# 51control.net
KiCad netlist of a schematic drawn in Altium Designer
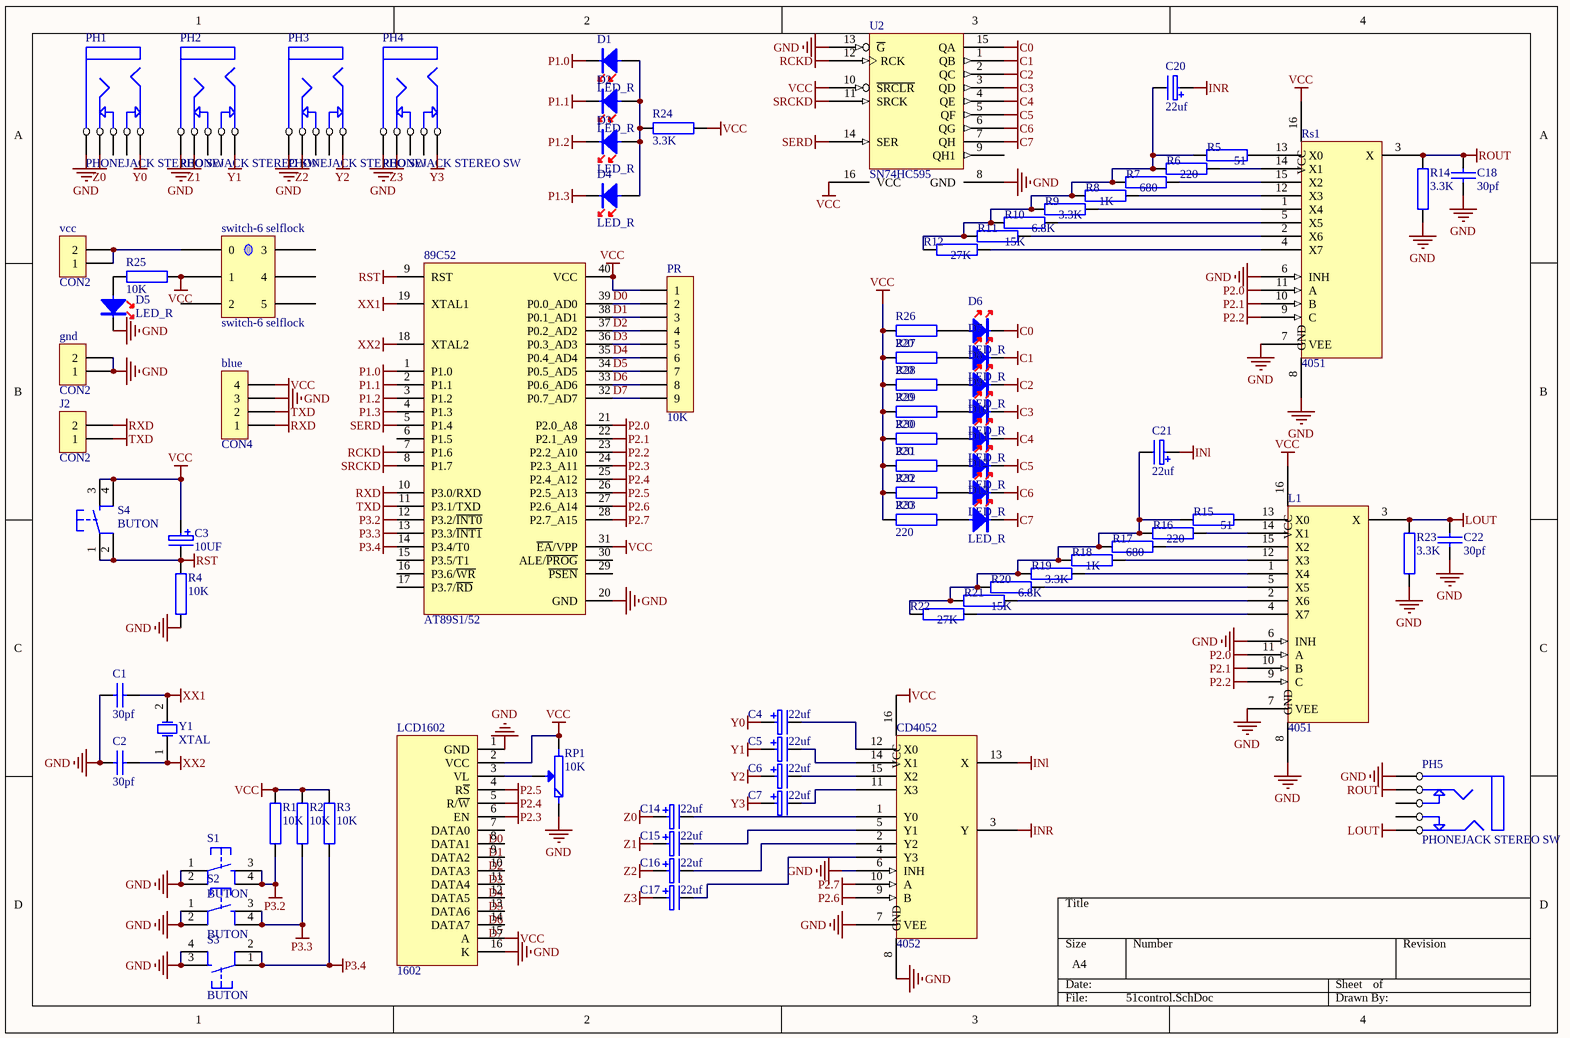
[diagram p0: 51control.SchDoc]

(export (version "E")
  (design (tool "Eeschema 10.0.6"))
  (components
    (comp (ref "89C52")
      (value "AT89S1/52")
      (footprint "DIP40")
      (description "8051/52单片机")
      (libsource (lib "常用元件集成库") (part "AT89S1/52"))
    )
    (comp (ref "blue")
      (value "CON4")
      (footprint "sip-4")
      (description "Connector")
      (libsource (lib "排针") (part "CON4"))
    )
    (comp (ref "C1") (value "30pf") (footprint "0603") (libsource (lib "电容") (part "CAP1")))
    (comp (ref "C2") (value "30pf") (footprint "0603") (libsource (lib "电容") (part "CAP1")))
    (comp (ref "C3") (value "10UF") (footprint "CAO2") (libsource (lib "电容") (part "CAP3")))
    (comp (ref "C4") (value "22uf") (footprint "CAO2") (libsource (lib "电容") (part "CAP3")))
    (comp (ref "C5") (value "22uf") (footprint "CAO2") (libsource (lib "电容") (part "CAP3")))
    (comp (ref "C6") (value "22uf") (footprint "CAO2") (libsource (lib "电容") (part "CAP3")))
    (comp (ref "C7") (value "22uf") (footprint "CAO2") (libsource (lib "电容") (part "CAP3")))
    (comp (ref "C14") (value "22uf") (footprint "CAO2") (libsource (lib "电容") (part "CAP3")))
    (comp (ref "C15") (value "22uf") (footprint "CAO2") (libsource (lib "电容") (part "CAP3")))
    (comp (ref "C16") (value "22uf") (footprint "CAO2") (libsource (lib "电容") (part "CAP3")))
    (comp (ref "C17") (value "22uf") (footprint "CAO2") (libsource (lib "电容") (part "CAP3")))
    (comp (ref "C18") (value "30pf") (footprint "0603") (libsource (lib "电容") (part "CAP1")))
    (comp (ref "C20") (value "22uf") (footprint "CAO2") (libsource (lib "电容") (part "CAP3")))
    (comp (ref "C21") (value "22uf") (footprint "CAO2") (libsource (lib "电容") (part "CAP3")))
    (comp (ref "C22") (value "30pf") (footprint "0603") (libsource (lib "电容") (part "CAP1")))
    (comp (ref "CD4052") (value "4052") (footprint "CD4052") (libsource (lib "常用元件原理图库") (part "4052")))
    (comp (ref "D1") (value "LED_R") (footprint "LED2_R") (libsource (lib "Diode二极管") (part "LED_R")))
    (comp (ref "D2") (value "LED_R") (footprint "LED2_R") (libsource (lib "Diode二极管") (part "LED_R")))
    (comp (ref "D3") (value "LED_R") (footprint "LED2_R") (libsource (lib "Diode二极管") (part "LED_R")))
    (comp (ref "D4") (value "LED_R") (footprint "LED2_R") (libsource (lib "Diode二极管") (part "LED_R")))
    (comp (ref "D5") (value "LED_R") (footprint "LED_0805") (libsource (lib "Diode二极管") (part "LED_R")))
    (comp (ref "D6") (value "LED_R") (footprint "LED_0805") (libsource (lib "Diode二极管") (part "LED_R")))
    (comp (ref "D7") (value "LED_R") (footprint "LED_0805") (libsource (lib "Diode二极管") (part "LED_R")))
    (comp (ref "D8") (value "LED_R") (footprint "LED_0805") (libsource (lib "Diode二极管") (part "LED_R")))
    (comp (ref "D9") (value "LED_R") (footprint "LED_0805") (libsource (lib "Diode二极管") (part "LED_R")))
    (comp (ref "D10") (value "LED_R") (footprint "LED_0805") (libsource (lib "Diode二极管") (part "LED_R")))
    (comp (ref "D11") (value "LED_R") (footprint "LED_0805") (libsource (lib "Diode二极管") (part "LED_R")))
    (comp (ref "D12") (value "LED_R") (footprint "LED_0805") (libsource (lib "Diode二极管") (part "LED_R")))
    (comp (ref "D13") (value "LED_R") (footprint "LED_0805") (libsource (lib "Diode二极管") (part "LED_R")))
    (comp (ref "gnd")
      (value "CON2")
      (footprint "2P-200")
      (description "Connector")
      (libsource (lib "排针") (part "CON2"))
    )
    (comp (ref "J2")
      (value "CON2")
      (footprint "sip-2")
      (description "Connector")
      (libsource (lib "排针") (part "CON2"))
    )
    (comp (ref "L1") (value "4051") (footprint "CD4051 NSG") (libsource (lib "CD4000系列IC") (part "4051")))
    (comp (ref "LCD1602") (value "1602") (footprint "1602A") (libsource (lib "液晶_数码管") (part "1602")))
    (comp (ref "PH1")
      (value "PHONEJACK STEREO SW")
      (footprint "SOUND1")
      (libsource (lib "Plugs插头") (part "PHONEJACK STEREO SW"))
    )
    (comp (ref "PH2")
      (value "PHONEJACK STEREO SW")
      (footprint "SOUND1")
      (libsource (lib "Plugs插头") (part "PHONEJACK STEREO SW"))
    )
    (comp (ref "PH3")
      (value "PHONEJACK STEREO SW")
      (footprint "SOUND1")
      (libsource (lib "Plugs插头") (part "PHONEJACK STEREO SW"))
    )
    (comp (ref "PH4")
      (value "PHONEJACK STEREO SW")
      (footprint "SOUND1")
      (libsource (lib "Plugs插头") (part "PHONEJACK STEREO SW"))
    )
    (comp (ref "PH5")
      (value "PHONEJACK STEREO SW")
      (footprint "SOUND1")
      (libsource (lib "Plugs插头") (part "PHONEJACK STEREO SW"))
    )
    (comp (ref "PR")
      (value "10K")
      (footprint "sip-9")
      (description "Connector")
      (libsource (lib "排针") (part "CON9"))
    )
    (comp (ref "R1") (value "10K") (footprint "0603") (description "电阻") (libsource (lib "电阻") (part "RES")))
    (comp (ref "R2") (value "10K") (footprint "0603") (description "电阻") (libsource (lib "电阻") (part "RES")))
    (comp (ref "R3") (value "10K") (footprint "0603") (description "电阻") (libsource (lib "电阻") (part "RES")))
    (comp (ref "R4") (value "10K") (footprint "0603") (description "电阻") (libsource (lib "电阻") (part "RES")))
    (comp (ref "R5") (value "51") (footprint "0805") (description "电阻") (libsource (lib "电阻") (part "RES")))
    (comp (ref "R6") (value "220") (footprint "0805") (description "电阻") (libsource (lib "电阻") (part "RES")))
    (comp (ref "R7") (value "680") (footprint "0805") (description "电阻") (libsource (lib "电阻") (part "RES")))
    (comp (ref "R8") (value "1K") (footprint "0805") (description "电阻") (libsource (lib "电阻") (part "RES")))
    (comp (ref "R9") (value "3.3K") (footprint "0805") (description "电阻") (libsource (lib "电阻") (part "RES")))
    (comp (ref "R10")
      (value "6.8K")
      (footprint "0805")
      (description "电阻")
      (libsource (lib "电阻") (part "RES"))
    )
    (comp (ref "R11") (value "15K") (footprint "0805") (description "电阻") (libsource (lib "电阻") (part "RES")))
    (comp (ref "R12") (value "27K") (footprint "0805") (description "电阻") (libsource (lib "电阻") (part "RES")))
    (comp (ref "R14")
      (value "3.3K")
      (footprint "0805")
      (description "电阻")
      (libsource (lib "电阻") (part "RES"))
    )
    (comp (ref "R15") (value "51") (footprint "0805") (description "电阻") (libsource (lib "电阻") (part "RES")))
    (comp (ref "R16") (value "220") (footprint "0805") (description "电阻") (libsource (lib "电阻") (part "RES")))
    (comp (ref "R17") (value "680") (footprint "0805") (description "电阻") (libsource (lib "电阻") (part "RES")))
    (comp (ref "R18") (value "1K") (footprint "0805") (description "电阻") (libsource (lib "电阻") (part "RES")))
    (comp (ref "R19")
      (value "3.3K")
      (footprint "0805")
      (description "电阻")
      (libsource (lib "电阻") (part "RES"))
    )
    (comp (ref "R20")
      (value "6.8K")
      (footprint "0805")
      (description "电阻")
      (libsource (lib "电阻") (part "RES"))
    )
    (comp (ref "R21") (value "15K") (footprint "0805") (description "电阻") (libsource (lib "电阻") (part "RES")))
    (comp (ref "R22") (value "27K") (footprint "0805") (description "电阻") (libsource (lib "电阻") (part "RES")))
    (comp (ref "R23")
      (value "3.3K")
      (footprint "0805")
      (description "电阻")
      (libsource (lib "电阻") (part "RES"))
    )
    (comp (ref "R24")
      (value "3.3K")
      (footprint "0805")
      (description "电阻")
      (libsource (lib "电阻") (part "RES"))
    )
    (comp (ref "R25") (value "10K") (footprint "0603") (description "电阻") (libsource (lib "电阻") (part "RES")))
    (comp (ref "R26") (value "220") (footprint "0805") (description "电阻") (libsource (lib "电阻") (part "RES")))
    (comp (ref "R27") (value "220") (footprint "0805") (description "电阻") (libsource (lib "电阻") (part "RES")))
    (comp (ref "R28") (value "220") (footprint "0805") (description "电阻") (libsource (lib "电阻") (part "RES")))
    (comp (ref "R29") (value "220") (footprint "0805") (description "电阻") (libsource (lib "电阻") (part "RES")))
    (comp (ref "R30") (value "220") (footprint "0805") (description "电阻") (libsource (lib "电阻") (part "RES")))
    (comp (ref "R31") (value "220") (footprint "0805") (description "电阻") (libsource (lib "电阻") (part "RES")))
    (comp (ref "R32") (value "220") (footprint "0805") (description "电阻") (libsource (lib "电阻") (part "RES")))
    (comp (ref "R33") (value "220") (footprint "0805") (description "电阻") (libsource (lib "电阻") (part "RES")))
    (comp (ref "RP1")
      (value "10K")
      (footprint "RVR-2")
      (description "普通电位器")
      (libsource (lib "电阻") (part "RPOT-1"))
    )
    (comp (ref "Rs1") (value "4051") (footprint "CD4051 NSG") (libsource (lib "CD4000系列IC") (part "4051")))
    (comp (ref "S1") (value "BUTON") (footprint "TACTILE-PTH") (libsource (lib "常用元件集成库") (part "BUTON")))
    (comp (ref "S2") (value "BUTON") (footprint "TACTILE-PTH") (libsource (lib "常用元件集成库") (part "BUTON")))
    (comp (ref "S3") (value "BUTON") (footprint "TACTILE-PTH") (libsource (lib "常用元件集成库") (part "BUTON")))
    (comp (ref "S4") (value "BUTON") (footprint "TACTILE-PTH") (libsource (lib "常用元件集成库") (part "BUTON")))
    (comp (ref "switch-6 selflock")
      (value "switch-6 selflock")
      (footprint "switch-6 lockself")
      (libsource (lib "六脚自锁开关") (part "Component_1"))
    )
    (comp (ref "U2")
      (value "SN74HC595")
      (footprint "SO16")
      (description "8-BIT SFT REG WIRTH OUTPUT LCH")
      (libsource (lib "TTL74系列") (part "SN74HC595"))
    )
    (comp (ref "vcc")
      (value "CON2")
      (footprint "2P-200")
      (description "Connector")
      (libsource (lib "排针") (part "CON2"))
    )
    (comp (ref "Y1")
      (value "XTAL")
      (footprint "XTAL-RAD-0.2")
      (description "晶体振荡器")
      (fields (field (name "PUBLISHER") "Altium Limited"))
      (libsource (lib "常用元件集成库") (part "XTAL"))
    )
  )
  (nets
    (net (code "1") (name "/D0") (class "Default")
      (node (ref "89C52") (pin "39") (pinfunction "P0.0_AD0_39") (pintype "passive"))
      (node (ref "LCD1602") (pin "7") (pinfunction "DATA0_7") (pintype "passive"))
      (node (ref "PR") (pin "2") (pinfunction "2_2") (pintype "passive"))
    )
    (net (code "2") (name "/D1") (class "Default")
      (node (ref "89C52") (pin "38") (pinfunction "P0.1_AD1_38") (pintype "passive"))
      (node (ref "LCD1602") (pin "8") (pinfunction "DATA1_8") (pintype "passive"))
      (node (ref "PR") (pin "3") (pinfunction "3_3") (pintype "passive"))
    )
    (net (code "3") (name "/D2") (class "Default")
      (node (ref "89C52") (pin "37") (pinfunction "P0.2_AD2_37") (pintype "passive"))
      (node (ref "LCD1602") (pin "9") (pinfunction "DATA2_9") (pintype "passive"))
      (node (ref "PR") (pin "4") (pinfunction "4_4") (pintype "passive"))
    )
    (net (code "4") (name "/D3") (class "Default")
      (node (ref "89C52") (pin "36") (pinfunction "P0.3_AD3_36") (pintype "passive"))
      (node (ref "LCD1602") (pin "10") (pinfunction "DATA3_10") (pintype "passive"))
      (node (ref "PR") (pin "5") (pinfunction "5_5") (pintype "passive"))
    )
    (net (code "5") (name "/D4") (class "Default")
      (node (ref "89C52") (pin "35") (pinfunction "P0.4_AD4_35") (pintype "passive"))
      (node (ref "LCD1602") (pin "11") (pinfunction "DATA4_11") (pintype "passive"))
      (node (ref "PR") (pin "6") (pinfunction "6_6") (pintype "passive"))
    )
    (net (code "6") (name "/D5") (class "Default")
      (node (ref "89C52") (pin "34") (pinfunction "P0.5_AD5_34") (pintype "passive"))
      (node (ref "LCD1602") (pin "12") (pinfunction "DATA5_12") (pintype "passive"))
      (node (ref "PR") (pin "7") (pinfunction "7_7") (pintype "passive"))
    )
    (net (code "7") (name "/D6") (class "Default")
      (node (ref "89C52") (pin "33") (pinfunction "P0.6_AD6_33") (pintype "passive"))
      (node (ref "LCD1602") (pin "13") (pinfunction "DATA6_13") (pintype "passive"))
      (node (ref "PR") (pin "8") (pinfunction "8_8") (pintype "passive"))
    )
    (net (code "8") (name "/D7") (class "Default")
      (node (ref "89C52") (pin "32") (pinfunction "P0.7_AD7_32") (pintype "passive"))
      (node (ref "LCD1602") (pin "14") (pinfunction "DATA7_14") (pintype "passive"))
      (node (ref "PR") (pin "9") (pinfunction "9_9") (pintype "passive"))
    )
    (net (code "9") (name "C0") (class "Default")
      (node (ref "D6") (pin "2") (pinfunction "2_2") (pintype "passive"))
      (node (ref "U2") (pin "15") (pinfunction "QA_15") (pintype "tri_state"))
    )
    (net (code "10") (name "C1") (class "Default")
      (node (ref "D7") (pin "2") (pinfunction "2_2") (pintype "passive"))
      (node (ref "U2") (pin "1") (pinfunction "QB_1") (pintype "output"))
    )
    (net (code "11") (name "C2") (class "Default")
      (node (ref "D8") (pin "2") (pinfunction "2_2") (pintype "passive"))
      (node (ref "U2") (pin "2") (pinfunction "QC_2") (pintype "output"))
    )
    (net (code "12") (name "C3") (class "Default")
      (node (ref "D9") (pin "2") (pinfunction "2_2") (pintype "passive"))
      (node (ref "U2") (pin "3") (pinfunction "QD_3") (pintype "output"))
    )
    (net (code "13") (name "C4") (class "Default")
      (node (ref "D10") (pin "2") (pinfunction "2_2") (pintype "passive"))
      (node (ref "U2") (pin "4") (pinfunction "QE_4") (pintype "output"))
    )
    (net (code "14") (name "C5") (class "Default")
      (node (ref "D11") (pin "2") (pinfunction "2_2") (pintype "passive"))
      (node (ref "U2") (pin "5") (pinfunction "QF_5") (pintype "output"))
    )
    (net (code "15") (name "C6") (class "Default")
      (node (ref "D12") (pin "2") (pinfunction "2_2") (pintype "passive"))
      (node (ref "U2") (pin "6") (pinfunction "QG_6") (pintype "output"))
    )
    (net (code "16") (name "C7") (class "Default")
      (node (ref "D13") (pin "2") (pinfunction "2_2") (pintype "passive"))
      (node (ref "U2") (pin "7") (pinfunction "QH_7") (pintype "tri_state"))
    )
    (net (code "17") (name "GND") (class "Default")
      (node (ref "89C52") (pin "20") (pinfunction "GND_20") (pintype "passive"))
      (node (ref "C1") (pin "2") (pinfunction "2_2") (pintype "passive"))
      (node (ref "C18") (pin "2") (pinfunction "2_2") (pintype "passive"))
      (node (ref "C2") (pin "2") (pinfunction "2_2") (pintype "passive"))
      (node (ref "C22") (pin "2") (pinfunction "2_2") (pintype "passive"))
      (node (ref "CD4052") (pin "6") (pinfunction "INH_6") (pintype "input"))
      (node (ref "CD4052") (pin "7") (pinfunction "VEE_7") (pintype "passive"))
      (node (ref "CD4052") (pin "8") (pinfunction "GND_8") (pintype "power_in"))
      (node (ref "D5") (pin "2") (pinfunction "2_2") (pintype "passive"))
      (node (ref "L1") (pin "6") (pinfunction "INH_6") (pintype "input"))
      (node (ref "L1") (pin "7") (pinfunction "VEE_7") (pintype "passive"))
      (node (ref "L1") (pin "8") (pinfunction "GND_8") (pintype "power_in"))
      (node (ref "LCD1602") (pin "1") (pinfunction "GND_1") (pintype "passive"))
      (node (ref "LCD1602") (pin "16") (pinfunction "K_16") (pintype "passive"))
      (node (ref "PH1") (pin "5") (pinfunction "E_5") (pintype "passive"))
      (node (ref "PH2") (pin "5") (pinfunction "E_5") (pintype "passive"))
      (node (ref "PH3") (pin "5") (pinfunction "E_5") (pintype "passive"))
      (node (ref "PH4") (pin "5") (pinfunction "E_5") (pintype "passive"))
      (node (ref "PH5") (pin "5") (pinfunction "E_5") (pintype "passive"))
      (node (ref "R14") (pin "1") (pinfunction "1_1") (pintype "passive"))
      (node (ref "R23") (pin "1") (pinfunction "1_1") (pintype "passive"))
      (node (ref "R4") (pin "2") (pinfunction "2_2") (pintype "passive"))
      (node (ref "RP1") (pin "1") (pinfunction "1_1") (pintype "passive"))
      (node (ref "Rs1") (pin "6") (pinfunction "INH_6") (pintype "input"))
      (node (ref "Rs1") (pin "7") (pinfunction "VEE_7") (pintype "passive"))
      (node (ref "Rs1") (pin "8") (pinfunction "GND_8") (pintype "power_in"))
      (node (ref "S1") (pin "1") (pinfunction "1_1") (pintype "passive"))
      (node (ref "S1") (pin "2") (pinfunction "2_2") (pintype "passive"))
      (node (ref "S2") (pin "1") (pinfunction "1_1") (pintype "passive"))
      (node (ref "S2") (pin "2") (pinfunction "2_2") (pintype "passive"))
      (node (ref "S3") (pin "3") (pinfunction "3_3") (pintype "passive"))
      (node (ref "S3") (pin "4") (pinfunction "4_4") (pintype "passive"))
      (node (ref "U2") (pin "13") (pinfunction "~{G}_13") (pintype "input"))
      (node (ref "U2") (pin "8") (pinfunction "GND_8") (pintype "power_in"))
      (node (ref "blue") (pin "3") (pinfunction "3_3") (pintype "passive"))
      (node (ref "gnd") (pin "1") (pinfunction "1_1") (pintype "passive"))
      (node (ref "gnd") (pin "2") (pinfunction "2_2") (pintype "passive"))
    )
    (net (code "18") (name "INR") (class "Default")
      (node (ref "C20") (pin "1") (pintype "passive"))
      (node (ref "CD4052") (pin "3") (pinfunction "Y_3") (pintype "passive"))
    )
    (net (code "19") (name "INl") (class "Default")
      (node (ref "C21") (pin "1") (pintype "passive"))
      (node (ref "CD4052") (pin "13") (pinfunction "X_13") (pintype "passive"))
    )
    (net (code "20") (name "LOUT") (class "Default")
      (node (ref "C22") (pin "1") (pinfunction "1_1") (pintype "passive"))
      (node (ref "L1") (pin "3") (pinfunction "X_3") (pintype "passive"))
      (node (ref "PH5") (pin "1") (pinfunction "A_1") (pintype "passive"))
      (node (ref "R23") (pin "2") (pinfunction "2_2") (pintype "passive"))
    )
    (net (code "21") (name "Net-(C20-Pad2)") (class "Default")
      (node (ref "C20") (pin "2") (pintype "passive"))
      (node (ref "R10") (pin "1") (pinfunction "1_1") (pintype "passive"))
      (node (ref "R11") (pin "1") (pinfunction "1_1") (pintype "passive"))
      (node (ref "R12") (pin "1") (pinfunction "1_1") (pintype "passive"))
      (node (ref "R5") (pin "1") (pinfunction "1_1") (pintype "passive"))
      (node (ref "R6") (pin "1") (pinfunction "1_1") (pintype "passive"))
      (node (ref "R7") (pin "1") (pinfunction "1_1") (pintype "passive"))
      (node (ref "R8") (pin "1") (pinfunction "1_1") (pintype "passive"))
      (node (ref "R9") (pin "1") (pinfunction "1_1") (pintype "passive"))
    )
    (net (code "22") (name "Net-(C21-Pad2)") (class "Default")
      (node (ref "C21") (pin "2") (pintype "passive"))
      (node (ref "R15") (pin "1") (pinfunction "1_1") (pintype "passive"))
      (node (ref "R16") (pin "1") (pinfunction "1_1") (pintype "passive"))
      (node (ref "R17") (pin "1") (pinfunction "1_1") (pintype "passive"))
      (node (ref "R18") (pin "1") (pinfunction "1_1") (pintype "passive"))
      (node (ref "R19") (pin "1") (pinfunction "1_1") (pintype "passive"))
      (node (ref "R20") (pin "1") (pinfunction "1_1") (pintype "passive"))
      (node (ref "R21") (pin "1") (pinfunction "1_1") (pintype "passive"))
      (node (ref "R22") (pin "1") (pinfunction "1_1") (pintype "passive"))
    )
    (net (code "23") (name "Net-(CD4052-X0)") (class "Default")
      (node (ref "C4") (pin "2") (pintype "passive"))
      (node (ref "CD4052") (pin "12") (pinfunction "X0_12") (pintype "passive"))
    )
    (net (code "24") (name "Net-(CD4052-X1)") (class "Default")
      (node (ref "C5") (pin "2") (pintype "passive"))
      (node (ref "CD4052") (pin "14") (pinfunction "X1_14") (pintype "passive"))
    )
    (net (code "25") (name "Net-(CD4052-X2)") (class "Default")
      (node (ref "C6") (pin "2") (pintype "passive"))
      (node (ref "CD4052") (pin "15") (pinfunction "X2_15") (pintype "passive"))
    )
    (net (code "26") (name "Net-(CD4052-X3)") (class "Default")
      (node (ref "C7") (pin "2") (pintype "passive"))
      (node (ref "CD4052") (pin "11") (pinfunction "X3_11") (pintype "passive"))
    )
    (net (code "27") (name "Net-(CD4052-Y0)") (class "Default")
      (node (ref "C14") (pin "2") (pintype "passive"))
      (node (ref "CD4052") (pin "1") (pinfunction "Y0_1") (pintype "passive"))
    )
    (net (code "28") (name "Net-(CD4052-Y1)") (class "Default")
      (node (ref "C15") (pin "2") (pintype "passive"))
      (node (ref "CD4052") (pin "5") (pinfunction "Y1_5") (pintype "passive"))
    )
    (net (code "29") (name "Net-(CD4052-Y2)") (class "Default")
      (node (ref "C16") (pin "2") (pintype "passive"))
      (node (ref "CD4052") (pin "2") (pinfunction "Y2_2") (pintype "passive"))
    )
    (net (code "30") (name "Net-(CD4052-Y3)") (class "Default")
      (node (ref "C17") (pin "2") (pintype "passive"))
      (node (ref "CD4052") (pin "4") (pinfunction "Y3_4") (pintype "passive"))
    )
    (net (code "31") (name "Net-(D1-Pad1)") (class "Default")
      (node (ref "D1") (pin "1") (pinfunction "1_1") (pintype "passive"))
      (node (ref "D2") (pin "1") (pinfunction "1_1") (pintype "passive"))
      (node (ref "D3") (pin "1") (pinfunction "1_1") (pintype "passive"))
      (node (ref "D4") (pin "1") (pinfunction "1_1") (pintype "passive"))
      (node (ref "R24") (pin "2") (pinfunction "2_2") (pintype "passive"))
    )
    (net (code "32") (name "Net-(D5-Pad1)") (class "Default")
      (node (ref "D5") (pin "1") (pinfunction "1_1") (pintype "passive"))
      (node (ref "R25") (pin "1") (pinfunction "1_1") (pintype "passive"))
    )
    (net (code "33") (name "Net-(D6-Pad1)") (class "Default")
      (node (ref "D6") (pin "1") (pinfunction "1_1") (pintype "passive"))
      (node (ref "R26") (pin "1") (pinfunction "1_1") (pintype "passive"))
    )
    (net (code "34") (name "Net-(D7-Pad1)") (class "Default")
      (node (ref "D7") (pin "1") (pinfunction "1_1") (pintype "passive"))
      (node (ref "R27") (pin "1") (pinfunction "1_1") (pintype "passive"))
    )
    (net (code "35") (name "Net-(D8-Pad1)") (class "Default")
      (node (ref "D8") (pin "1") (pinfunction "1_1") (pintype "passive"))
      (node (ref "R28") (pin "1") (pinfunction "1_1") (pintype "passive"))
    )
    (net (code "36") (name "Net-(D9-Pad1)") (class "Default")
      (node (ref "D9") (pin "1") (pinfunction "1_1") (pintype "passive"))
      (node (ref "R29") (pin "1") (pinfunction "1_1") (pintype "passive"))
    )
    (net (code "37") (name "Net-(D10-Pad1)") (class "Default")
      (node (ref "D10") (pin "1") (pinfunction "1_1") (pintype "passive"))
      (node (ref "R30") (pin "1") (pinfunction "1_1") (pintype "passive"))
    )
    (net (code "38") (name "Net-(D11-Pad1)") (class "Default")
      (node (ref "D11") (pin "1") (pinfunction "1_1") (pintype "passive"))
      (node (ref "R31") (pin "1") (pinfunction "1_1") (pintype "passive"))
    )
    (net (code "39") (name "Net-(D12-Pad1)") (class "Default")
      (node (ref "D12") (pin "1") (pinfunction "1_1") (pintype "passive"))
      (node (ref "R32") (pin "1") (pinfunction "1_1") (pintype "passive"))
    )
    (net (code "40") (name "Net-(D13-Pad1)") (class "Default")
      (node (ref "D13") (pin "1") (pinfunction "1_1") (pintype "passive"))
      (node (ref "R33") (pin "1") (pinfunction "1_1") (pintype "passive"))
    )
    (net (code "41") (name "Net-(L1-X0)") (class "Default")
      (node (ref "L1") (pin "13") (pinfunction "X0_13") (pintype "passive"))
      (node (ref "R15") (pin "2") (pinfunction "2_2") (pintype "passive"))
    )
    (net (code "42") (name "Net-(L1-X1)") (class "Default")
      (node (ref "L1") (pin "14") (pinfunction "X1_14") (pintype "passive"))
      (node (ref "R16") (pin "2") (pinfunction "2_2") (pintype "passive"))
    )
    (net (code "43") (name "Net-(L1-X2)") (class "Default")
      (node (ref "L1") (pin "15") (pinfunction "X2_15") (pintype "passive"))
      (node (ref "R17") (pin "2") (pinfunction "2_2") (pintype "passive"))
    )
    (net (code "44") (name "Net-(L1-X3)") (class "Default")
      (node (ref "L1") (pin "12") (pinfunction "X3_12") (pintype "passive"))
      (node (ref "R18") (pin "2") (pinfunction "2_2") (pintype "passive"))
    )
    (net (code "45") (name "Net-(L1-X4)") (class "Default")
      (node (ref "L1") (pin "1") (pinfunction "X4_1") (pintype "passive"))
      (node (ref "R19") (pin "2") (pinfunction "2_2") (pintype "passive"))
    )
    (net (code "46") (name "Net-(L1-X5)") (class "Default")
      (node (ref "L1") (pin "5") (pinfunction "X5_5") (pintype "passive"))
      (node (ref "R20") (pin "2") (pinfunction "2_2") (pintype "passive"))
    )
    (net (code "47") (name "Net-(L1-X6)") (class "Default")
      (node (ref "L1") (pin "2") (pinfunction "X6_2") (pintype "passive"))
      (node (ref "R21") (pin "2") (pinfunction "2_2") (pintype "passive"))
    )
    (net (code "48") (name "Net-(L1-X7)") (class "Default")
      (node (ref "L1") (pin "4") (pinfunction "X7_4") (pintype "passive"))
      (node (ref "R22") (pin "2") (pinfunction "2_2") (pintype "passive"))
    )
    (net (code "49") (name "Net-(LCD1602-VL)") (class "Default")
      (node (ref "LCD1602") (pin "3") (pinfunction "VL_3") (pintype "passive"))
      (node (ref "RP1") (pin "2") (pinfunction "M_2") (pintype "passive"))
    )
    (net (code "50") (name "Net-(Rs1-X0)") (class "Default")
      (node (ref "R5") (pin "2") (pinfunction "2_2") (pintype "passive"))
      (node (ref "Rs1") (pin "13") (pinfunction "X0_13") (pintype "passive"))
    )
    (net (code "51") (name "Net-(Rs1-X1)") (class "Default")
      (node (ref "R6") (pin "2") (pinfunction "2_2") (pintype "passive"))
      (node (ref "Rs1") (pin "14") (pinfunction "X1_14") (pintype "passive"))
    )
    (net (code "52") (name "Net-(Rs1-X2)") (class "Default")
      (node (ref "R7") (pin "2") (pinfunction "2_2") (pintype "passive"))
      (node (ref "Rs1") (pin "15") (pinfunction "X2_15") (pintype "passive"))
    )
    (net (code "53") (name "Net-(Rs1-X3)") (class "Default")
      (node (ref "R8") (pin "2") (pinfunction "2_2") (pintype "passive"))
      (node (ref "Rs1") (pin "12") (pinfunction "X3_12") (pintype "passive"))
    )
    (net (code "54") (name "Net-(Rs1-X4)") (class "Default")
      (node (ref "R9") (pin "2") (pinfunction "2_2") (pintype "passive"))
      (node (ref "Rs1") (pin "1") (pinfunction "X4_1") (pintype "passive"))
    )
    (net (code "55") (name "Net-(Rs1-X5)") (class "Default")
      (node (ref "R10") (pin "2") (pinfunction "2_2") (pintype "passive"))
      (node (ref "Rs1") (pin "5") (pinfunction "X5_5") (pintype "passive"))
    )
    (net (code "56") (name "Net-(Rs1-X6)") (class "Default")
      (node (ref "R11") (pin "2") (pinfunction "2_2") (pintype "passive"))
      (node (ref "Rs1") (pin "2") (pinfunction "X6_2") (pintype "passive"))
    )
    (net (code "57") (name "Net-(Rs1-X7)") (class "Default")
      (node (ref "R12") (pin "2") (pinfunction "2_2") (pintype "passive"))
      (node (ref "Rs1") (pin "4") (pinfunction "X7_4") (pintype "passive"))
    )
    (net (code "58") (name "Net-(switch-6 selflock-Pad0)") (class "Default")
      (node (ref "switch-6 selflock") (pin "0") (pinfunction "0_0") (pintype "passive"))
      (node (ref "vcc") (pin "1") (pinfunction "1_1") (pintype "passive"))
      (node (ref "vcc") (pin "2") (pinfunction "2_2") (pintype "passive"))
    )
    (net (code "59") (name "P1.0") (class "Default")
      (node (ref "89C52") (pin "1") (pinfunction "P1.0_1") (pintype "passive"))
      (node (ref "D1") (pin "2") (pinfunction "2_2") (pintype "passive"))
    )
    (net (code "60") (name "P1.1") (class "Default")
      (node (ref "89C52") (pin "2") (pinfunction "P1.1_2") (pintype "passive"))
      (node (ref "D2") (pin "2") (pinfunction "2_2") (pintype "passive"))
    )
    (net (code "61") (name "P1.2") (class "Default")
      (node (ref "89C52") (pin "3") (pinfunction "P1.2_3") (pintype "passive"))
      (node (ref "D3") (pin "2") (pinfunction "2_2") (pintype "passive"))
    )
    (net (code "62") (name "P1.3") (class "Default")
      (node (ref "89C52") (pin "4") (pinfunction "P1.3_4") (pintype "passive"))
      (node (ref "D4") (pin "2") (pinfunction "2_2") (pintype "passive"))
    )
    (net (code "63") (name "P2.0") (class "Default")
      (node (ref "89C52") (pin "21") (pinfunction "P2.0_A8_21") (pintype "passive"))
      (node (ref "L1") (pin "11") (pinfunction "A_11") (pintype "input"))
      (node (ref "Rs1") (pin "11") (pinfunction "A_11") (pintype "input"))
    )
    (net (code "64") (name "P2.1") (class "Default")
      (node (ref "89C52") (pin "22") (pinfunction "P2.1_A9_22") (pintype "passive"))
      (node (ref "L1") (pin "10") (pinfunction "B_10") (pintype "input"))
      (node (ref "Rs1") (pin "10") (pinfunction "B_10") (pintype "input"))
    )
    (net (code "65") (name "P2.2") (class "Default")
      (node (ref "89C52") (pin "23") (pinfunction "P2.2_A10_23") (pintype "passive"))
      (node (ref "L1") (pin "9") (pinfunction "C_9") (pintype "input"))
      (node (ref "Rs1") (pin "9") (pinfunction "C_9") (pintype "input"))
    )
    (net (code "66") (name "P2.3") (class "Default")
      (node (ref "89C52") (pin "24") (pinfunction "P2.3_A11_24") (pintype "passive"))
      (node (ref "LCD1602") (pin "6") (pinfunction "EN_6") (pintype "passive"))
    )
    (net (code "67") (name "P2.4") (class "Default")
      (node (ref "89C52") (pin "25") (pinfunction "P2.4_A12_25") (pintype "passive"))
      (node (ref "LCD1602") (pin "5") (pinfunction "R/~{W}_5") (pintype "passive"))
    )
    (net (code "68") (name "P2.5") (class "Default")
      (node (ref "89C52") (pin "26") (pinfunction "P2.5_A13_26") (pintype "passive"))
      (node (ref "LCD1602") (pin "4") (pinfunction "R~{S}_4") (pintype "passive"))
    )
    (net (code "69") (name "P2.6") (class "Default")
      (node (ref "89C52") (pin "27") (pinfunction "P2.6_A14_27") (pintype "passive"))
      (node (ref "CD4052") (pin "9") (pinfunction "B_9") (pintype "input"))
    )
    (net (code "70") (name "P2.7") (class "Default")
      (node (ref "89C52") (pin "28") (pinfunction "P2.7_A15_28") (pintype "passive"))
      (node (ref "CD4052") (pin "10") (pinfunction "A_10") (pintype "input"))
    )
    (net (code "71") (name "P3.2") (class "Default")
      (node (ref "89C52") (pin "12") (pinfunction "P3.2/~{INT0}_12") (pintype "passive"))
      (node (ref "R1") (pin "1") (pinfunction "1_1") (pintype "passive"))
      (node (ref "S1") (pin "3") (pinfunction "3_3") (pintype "passive"))
      (node (ref "S1") (pin "4") (pinfunction "4_4") (pintype "passive"))
    )
    (net (code "72") (name "P3.3") (class "Default")
      (node (ref "89C52") (pin "13") (pinfunction "P3.3/~{INT1}_13") (pintype "passive"))
      (node (ref "R2") (pin "1") (pinfunction "1_1") (pintype "passive"))
      (node (ref "S2") (pin "3") (pinfunction "3_3") (pintype "passive"))
      (node (ref "S2") (pin "4") (pinfunction "4_4") (pintype "passive"))
    )
    (net (code "73") (name "P3.4") (class "Default")
      (node (ref "89C52") (pin "14") (pinfunction "P3.4/T0_14") (pintype "passive"))
      (node (ref "R3") (pin "1") (pinfunction "1_1") (pintype "passive"))
      (node (ref "S3") (pin "1") (pinfunction "1_1") (pintype "passive"))
      (node (ref "S3") (pin "2") (pinfunction "2_2") (pintype "passive"))
    )
    (net (code "74") (name "RCKD") (class "Default")
      (node (ref "89C52") (pin "7") (pinfunction "P1.6_7") (pintype "passive"))
      (node (ref "U2") (pin "12") (pinfunction "RCK_12") (pintype "input"))
    )
    (net (code "75") (name "ROUT") (class "Default")
      (node (ref "C18") (pin "1") (pinfunction "1_1") (pintype "passive"))
      (node (ref "PH5") (pin "4") (pinfunction "D_4") (pintype "passive"))
      (node (ref "R14") (pin "2") (pinfunction "2_2") (pintype "passive"))
      (node (ref "Rs1") (pin "3") (pinfunction "X_3") (pintype "passive"))
    )
    (net (code "76") (name "RST") (class "Default")
      (node (ref "89C52") (pin "9") (pinfunction "RST_9") (pintype "passive"))
      (node (ref "C3") (pin "2") (pintype "passive"))
      (node (ref "R4") (pin "1") (pinfunction "1_1") (pintype "passive"))
      (node (ref "S4") (pin "1") (pinfunction "1_1") (pintype "passive"))
      (node (ref "S4") (pin "2") (pinfunction "2_2") (pintype "passive"))
    )
    (net (code "77") (name "RXD") (class "Default")
      (node (ref "89C52") (pin "10") (pinfunction "P3.0/RXD_10") (pintype "passive"))
      (node (ref "J2") (pin "2") (pinfunction "2_2") (pintype "passive"))
      (node (ref "blue") (pin "1") (pinfunction "1_1") (pintype "passive"))
    )
    (net (code "78") (name "SERD") (class "Default")
      (node (ref "89C52") (pin "5") (pinfunction "P1.4_5") (pintype "passive"))
      (node (ref "U2") (pin "14") (pinfunction "SER_14") (pintype "input"))
    )
    (net (code "79") (name "SRCKD") (class "Default")
      (node (ref "89C52") (pin "8") (pinfunction "P1.7_8") (pintype "passive"))
      (node (ref "U2") (pin "11") (pinfunction "SRCK_11") (pintype "input"))
    )
    (net (code "80") (name "TXD") (class "Default")
      (node (ref "89C52") (pin "11") (pinfunction "P3.1/TXD_11") (pintype "passive"))
      (node (ref "J2") (pin "1") (pinfunction "1_1") (pintype "passive"))
      (node (ref "blue") (pin "2") (pinfunction "2_2") (pintype "passive"))
    )
    (net (code "81") (name "VCC") (class "Default")
      (node (ref "89C52") (pin "31") (pinfunction "~{EA}/VPP_31") (pintype "passive"))
      (node (ref "89C52") (pin "40") (pinfunction "VCC_40") (pintype "passive"))
      (node (ref "C3") (pin "1") (pintype "passive"))
      (node (ref "CD4052") (pin "16") (pinfunction "VCC_16") (pintype "power_in"))
      (node (ref "L1") (pin "16") (pinfunction "VCC_16") (pintype "power_in"))
      (node (ref "LCD1602") (pin "15") (pinfunction "A_15") (pintype "passive"))
      (node (ref "LCD1602") (pin "2") (pinfunction "VCC_2") (pintype "passive"))
      (node (ref "PR") (pin "1") (pinfunction "1_1") (pintype "passive"))
      (node (ref "R1") (pin "2") (pinfunction "2_2") (pintype "passive"))
      (node (ref "R2") (pin "2") (pinfunction "2_2") (pintype "passive"))
      (node (ref "R24") (pin "1") (pinfunction "1_1") (pintype "passive"))
      (node (ref "R25") (pin "2") (pinfunction "2_2") (pintype "passive"))
      (node (ref "R26") (pin "2") (pinfunction "2_2") (pintype "passive"))
      (node (ref "R27") (pin "2") (pinfunction "2_2") (pintype "passive"))
      (node (ref "R28") (pin "2") (pinfunction "2_2") (pintype "passive"))
      (node (ref "R29") (pin "2") (pinfunction "2_2") (pintype "passive"))
      (node (ref "R3") (pin "2") (pinfunction "2_2") (pintype "passive"))
      (node (ref "R30") (pin "2") (pinfunction "2_2") (pintype "passive"))
      (node (ref "R31") (pin "2") (pinfunction "2_2") (pintype "passive"))
      (node (ref "R32") (pin "2") (pinfunction "2_2") (pintype "passive"))
      (node (ref "R33") (pin "2") (pinfunction "2_2") (pintype "passive"))
      (node (ref "RP1") (pin "3") (pinfunction "3_3") (pintype "passive"))
      (node (ref "Rs1") (pin "16") (pinfunction "VCC_16") (pintype "power_in"))
      (node (ref "S4") (pin "3") (pinfunction "3_3") (pintype "passive"))
      (node (ref "S4") (pin "4") (pinfunction "4_4") (pintype "passive"))
      (node (ref "U2") (pin "10") (pinfunction "~{SRCLR}_10") (pintype "input"))
      (node (ref "U2") (pin "16") (pinfunction "VCC_16") (pintype "power_in"))
      (node (ref "blue") (pin "4") (pinfunction "4_4") (pintype "passive"))
      (node (ref "switch-6 selflock") (pin "1") (pinfunction "1_1") (pintype "passive"))
    )
    (net (code "82") (name "XX1") (class "Default")
      (node (ref "89C52") (pin "19") (pinfunction "XTAL1_19") (pintype "passive"))
      (node (ref "C1") (pin "1") (pinfunction "1_1") (pintype "passive"))
      (node (ref "Y1") (pin "2") (pinfunction "OSC2_2") (pintype "passive"))
    )
    (net (code "83") (name "XX2") (class "Default")
      (node (ref "89C52") (pin "18") (pinfunction "XTAL2_18") (pintype "passive"))
      (node (ref "C2") (pin "1") (pinfunction "1_1") (pintype "passive"))
      (node (ref "Y1") (pin "1") (pinfunction "OSC1_1") (pintype "passive"))
    )
    (net (code "84") (name "Y0") (class "Default")
      (node (ref "C4") (pin "1") (pintype "passive"))
      (node (ref "PH1") (pin "1") (pinfunction "A_1") (pintype "passive"))
    )
    (net (code "85") (name "Y1") (class "Default")
      (node (ref "C5") (pin "1") (pintype "passive"))
      (node (ref "PH2") (pin "1") (pinfunction "A_1") (pintype "passive"))
    )
    (net (code "86") (name "Y2") (class "Default")
      (node (ref "C6") (pin "1") (pintype "passive"))
      (node (ref "PH3") (pin "1") (pinfunction "A_1") (pintype "passive"))
    )
    (net (code "87") (name "Y3") (class "Default")
      (node (ref "C7") (pin "1") (pintype "passive"))
      (node (ref "PH4") (pin "1") (pinfunction "A_1") (pintype "passive"))
    )
    (net (code "88") (name "Z0") (class "Default")
      (node (ref "C14") (pin "1") (pintype "passive"))
      (node (ref "PH1") (pin "4") (pinfunction "D_4") (pintype "passive"))
    )
    (net (code "89") (name "Z1") (class "Default")
      (node (ref "C15") (pin "1") (pintype "passive"))
      (node (ref "PH2") (pin "4") (pinfunction "D_4") (pintype "passive"))
    )
    (net (code "90") (name "Z2") (class "Default")
      (node (ref "C16") (pin "1") (pintype "passive"))
      (node (ref "PH3") (pin "4") (pinfunction "D_4") (pintype "passive"))
    )
    (net (code "91") (name "Z3") (class "Default")
      (node (ref "C17") (pin "1") (pintype "passive"))
      (node (ref "PH4") (pin "4") (pinfunction "D_4") (pintype "passive"))
    )
    (net (code "92") (name "unconnected-(89C52-ALE{slash}~{PROG}-Pad30)") (class "Default")
      (node (ref "89C52") (pin "30") (pinfunction "ALE/~{PROG}_30") (pintype "passive"))
    )
    (net (code "93") (name "unconnected-(89C52-P1.5-Pad6)") (class "Default")
      (node (ref "89C52") (pin "6") (pinfunction "P1.5_6") (pintype "passive"))
    )
    (net (code "94") (name "unconnected-(89C52-P3.5{slash}T1-Pad15)") (class "Default")
      (node (ref "89C52") (pin "15") (pinfunction "P3.5/T1_15") (pintype "passive"))
    )
    (net (code "95") (name "unconnected-(89C52-P3.6{slash}~{WR}-Pad16)") (class "Default")
      (node (ref "89C52") (pin "16") (pinfunction "P3.6/~{WR}_16") (pintype "passive"))
    )
    (net (code "96") (name "unconnected-(89C52-P3.7{slash}~{RD}-Pad17)") (class "Default")
      (node (ref "89C52") (pin "17") (pinfunction "P3.7/~{RD}_17") (pintype "passive"))
    )
    (net (code "97") (name "unconnected-(89C52-~{PSEN}-Pad29)") (class "Default")
      (node (ref "89C52") (pin "29") (pinfunction "~{PSEN}_29") (pintype "passive"))
    )
    (net (code "98") (name "unconnected-(PH1-B-Pad2)") (class "Default")
      (node (ref "PH1") (pin "2") (pinfunction "B_2") (pintype "passive"))
    )
    (net (code "99") (name "unconnected-(PH1-C-Pad3)") (class "Default")
      (node (ref "PH1") (pin "3") (pinfunction "C_3") (pintype "passive"))
    )
    (net (code "100") (name "unconnected-(PH2-B-Pad2)") (class "Default")
      (node (ref "PH2") (pin "2") (pinfunction "B_2") (pintype "passive"))
    )
    (net (code "101") (name "unconnected-(PH2-C-Pad3)") (class "Default")
      (node (ref "PH2") (pin "3") (pinfunction "C_3") (pintype "passive"))
    )
    (net (code "102") (name "unconnected-(PH3-B-Pad2)") (class "Default")
      (node (ref "PH3") (pin "2") (pinfunction "B_2") (pintype "passive"))
    )
    (net (code "103") (name "unconnected-(PH3-C-Pad3)") (class "Default")
      (node (ref "PH3") (pin "3") (pinfunction "C_3") (pintype "passive"))
    )
    (net (code "104") (name "unconnected-(PH4-B-Pad2)") (class "Default")
      (node (ref "PH4") (pin "2") (pinfunction "B_2") (pintype "passive"))
    )
    (net (code "105") (name "unconnected-(PH4-C-Pad3)") (class "Default")
      (node (ref "PH4") (pin "3") (pinfunction "C_3") (pintype "passive"))
    )
    (net (code "106") (name "unconnected-(PH5-B-Pad2)") (class "Default")
      (node (ref "PH5") (pin "2") (pinfunction "B_2") (pintype "passive"))
    )
    (net (code "107") (name "unconnected-(PH5-C-Pad3)") (class "Default")
      (node (ref "PH5") (pin "3") (pinfunction "C_3") (pintype "passive"))
    )
    (net (code "108") (name "unconnected-(U2-QH1-Pad9)") (class "Default")
      (node (ref "U2") (pin "9") (pinfunction "QH1_9") (pintype "output"))
    )
    (net (code "109") (name "unconnected-(switch-6 selflock-Pad2)") (class "Default")
      (node (ref "switch-6 selflock") (pin "2") (pinfunction "2_2") (pintype "passive"))
    )
    (net (code "110") (name "unconnected-(switch-6 selflock-Pad3)") (class "Default")
      (node (ref "switch-6 selflock") (pin "3") (pinfunction "3_3") (pintype "passive"))
    )
    (net (code "111") (name "unconnected-(switch-6 selflock-Pad4)") (class "Default")
      (node (ref "switch-6 selflock") (pin "4") (pinfunction "4_4") (pintype "passive"))
    )
    (net (code "112") (name "unconnected-(switch-6 selflock-Pad5)") (class "Default")
      (node (ref "switch-6 selflock") (pin "5") (pinfunction "5_5") (pintype "passive"))
    )
  )
)
